# PCB_sterownika_pasek_LED.net
KiCad netlist of a schematic drawn in EAGLE
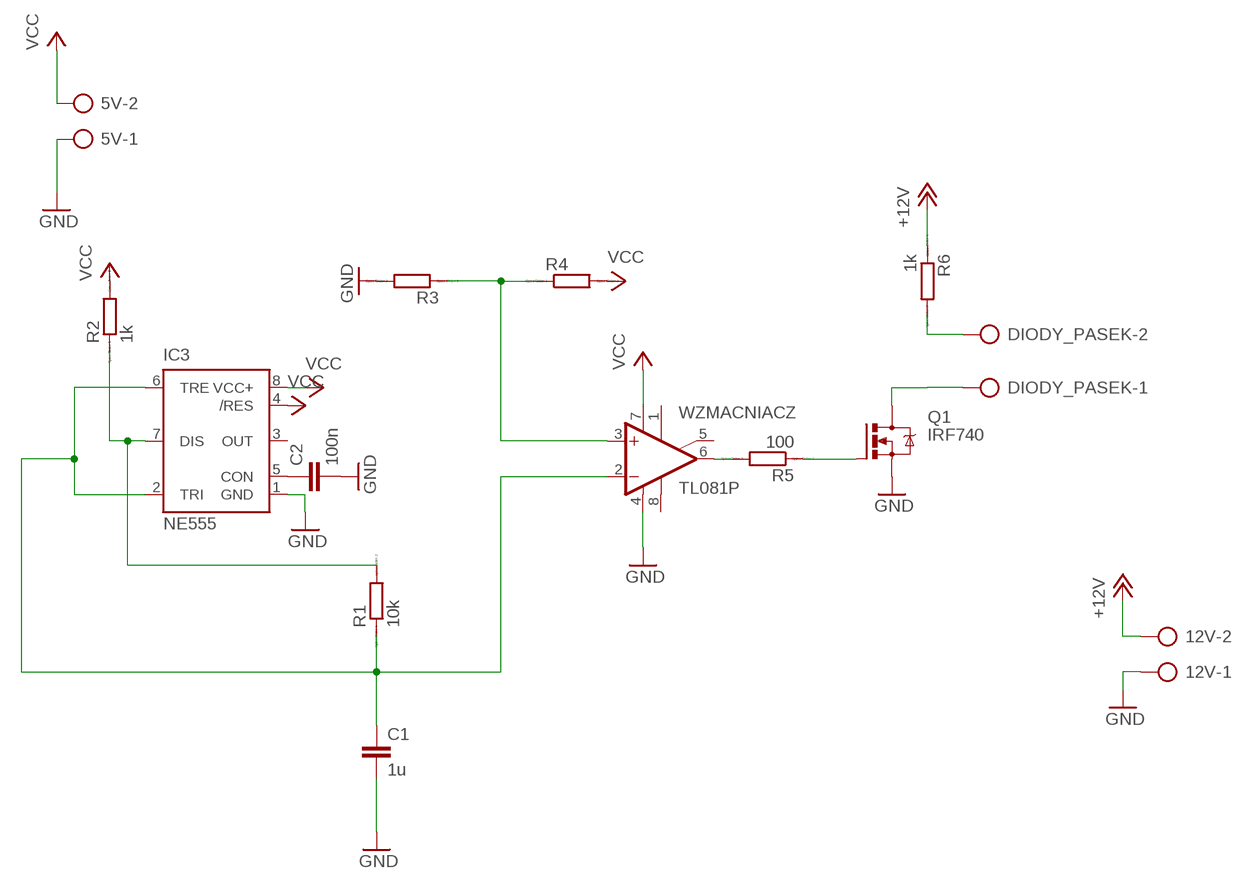
[diagram p0: schematic, sheet 1]

(export (version "E")
  (design (tool "Eeschema 10.0.6"))
  (components
    (comp (ref "5V")
      (value "AK500/2")
      (footprint "eagle-import:AK500_2")
      (libsource (lib "eagle-import") (part "AK500/2"))
    )
    (comp (ref "12V")
      (value "AK500/2")
      (footprint "eagle-import:AK500_2")
      (libsource (lib "eagle-import") (part "AK500/2"))
    )
    (comp (ref "C1")
      (value "1u")
      (footprint "eagle-import:C025-024X044")
      (libsource (lib "eagle-import") (part "C-EU025-024X044"))
    )
    (comp (ref "C2")
      (value "100n")
      (footprint "eagle-import:C025-024X044")
      (libsource (lib "eagle-import") (part "C-EU025-024X044"))
    )
    (comp (ref "DIODY_PASEK")
      (value "AK500/2")
      (footprint "eagle-import:AK500_2")
      (libsource (lib "eagle-import") (part "AK500/2"))
    )
    (comp (ref "IC3")
      (value "NE555")
      (footprint "eagle-import:DIL-08")
      (fields (field (name "MF") "Arrow Electronics") (field (name "MPN") "NE555N"))
      (libsource (lib "eagle-import") (part "NE555"))
    )
    (comp (ref "Q1")
      (value "IRF740")
      (footprint "eagle-import:TO220BV")
      (libsource (lib "eagle-import") (part "IRF740"))
    )
    (comp (ref "R1")
      (value "10k")
      (footprint "eagle-import:0204_7")
      (libsource (lib "eagle-import") (part "R0204/7"))
    )
    (comp (ref "R2")
      (value "1k")
      (footprint "eagle-import:0204_7")
      (libsource (lib "eagle-import") (part "R0204/7"))
    )
    (comp (ref "R3")
      (value "R0204/7")
      (footprint "eagle-import:0204_7")
      (libsource (lib "eagle-import") (part "R0204/7"))
    )
    (comp (ref "R4")
      (value "R0204/7")
      (footprint "eagle-import:0204_7")
      (libsource (lib "eagle-import") (part "R0204/7"))
    )
    (comp (ref "R5")
      (value "100")
      (footprint "eagle-import:0204_7")
      (libsource (lib "eagle-import") (part "R0204/7"))
    )
    (comp (ref "R6")
      (value "1k")
      (footprint "eagle-import:0204_7")
      (libsource (lib "eagle-import") (part "R0204/7"))
    )
    (comp (ref "WZMACNIACZ")
      (value "TL081P")
      (footprint "eagle-import:DIL08")
      (libsource (lib "eagle-import") (part "TL081P"))
    )
  )
  (nets
    (net (code "1") (name "+12V") (class "Default")
      (node (ref "12V") (pin "2") (pinfunction "KL_2") (pintype "passive"))
      (node (ref "R6") (pin "1") (pinfunction "1_1") (pintype "passive"))
    )
    (net (code "2") (name "GND") (class "Default")
      (node (ref "12V") (pin "1") (pinfunction "KL_1") (pintype "passive"))
      (node (ref "5V") (pin "1") (pinfunction "KL_1") (pintype "passive"))
      (node (ref "C1") (pin "2") (pinfunction "2_2") (pintype "passive"))
      (node (ref "C2") (pin "2") (pinfunction "2_2") (pintype "passive"))
      (node (ref "IC3") (pin "1") (pinfunction "GND_1") (pintype "power_in"))
      (node (ref "Q1") (pin "S") (pinfunction "S_S") (pintype "passive"))
      (node (ref "R3") (pin "2") (pinfunction "2_2") (pintype "passive"))
      (node (ref "WZMACNIACZ") (pin "4") (pinfunction "V-_4") (pintype "power_in"))
    )
    (net (code "3") (name "Net-(DIODY_PASEKA-KL)") (class "Default")
      (node (ref "DIODY_PASEK") (pin "1") (pinfunction "KL_1") (pintype "passive"))
      (node (ref "Q1") (pin "D") (pinfunction "D_D") (pintype "passive"))
    )
    (net (code "4") (name "Net-(DIODY_PASEKB-KL)") (class "Default")
      (node (ref "DIODY_PASEK") (pin "2") (pinfunction "KL_2") (pintype "passive"))
      (node (ref "R6") (pin "2") (pinfunction "2_2") (pintype "passive"))
    )
    (net (code "5") (name "Net-(IC3-CON)") (class "Default")
      (node (ref "C2") (pin "1") (pinfunction "1_1") (pintype "passive"))
      (node (ref "IC3") (pin "5") (pinfunction "CON_5") (pintype "input"))
    )
    (net (code "6") (name "Net-(IC3-DIS)") (class "Default")
      (node (ref "IC3") (pin "7") (pinfunction "DIS_7") (pintype "input"))
      (node (ref "R1") (pin "2") (pinfunction "2_2") (pintype "passive"))
      (node (ref "R2") (pin "1") (pinfunction "1_1") (pintype "passive"))
    )
    (net (code "7") (name "Net-(IC3-TRE)") (class "Default")
      (node (ref "C1") (pin "1") (pinfunction "1_1") (pintype "passive"))
      (node (ref "IC3") (pin "2") (pinfunction "TRI_2") (pintype "input"))
      (node (ref "IC3") (pin "6") (pinfunction "TRE_6") (pintype "input"))
      (node (ref "R1") (pin "1") (pinfunction "1_1") (pintype "passive"))
      (node (ref "WZMACNIACZ") (pin "2") (pinfunction "-IN_2") (pintype "input"))
    )
    (net (code "8") (name "Net-(Q1-PadG)") (class "Default")
      (node (ref "Q1") (pin "G") (pinfunction "G_G") (pintype "passive"))
      (node (ref "R5") (pin "1") (pinfunction "1_1") (pintype "passive"))
    )
    (net (code "9") (name "Net-(WZMACNIACZ-+IN)") (class "Default")
      (node (ref "R3") (pin "1") (pinfunction "1_1") (pintype "passive"))
      (node (ref "R4") (pin "1") (pinfunction "1_1") (pintype "passive"))
      (node (ref "WZMACNIACZ") (pin "3") (pinfunction "+IN_3") (pintype "input"))
    )
    (net (code "10") (name "Net-(WZMACNIACZ-OUT)") (class "Default")
      (node (ref "R5") (pin "2") (pinfunction "2_2") (pintype "passive"))
      (node (ref "WZMACNIACZ") (pin "6") (pinfunction "OUT_6") (pintype "output"))
    )
    (net (code "11") (name "VCC") (class "Default")
      (node (ref "5V") (pin "2") (pinfunction "KL_2") (pintype "passive"))
      (node (ref "IC3") (pin "4") (pinfunction "/RES_4") (pintype "input"))
      (node (ref "IC3") (pin "8") (pinfunction "VCC+_8") (pintype "power_in"))
      (node (ref "R2") (pin "2") (pinfunction "2_2") (pintype "passive"))
      (node (ref "R4") (pin "2") (pinfunction "2_2") (pintype "passive"))
      (node (ref "WZMACNIACZ") (pin "7") (pinfunction "V+_7") (pintype "power_in"))
    )
    (net (code "12") (name "unconnected-(IC3-OUT-Pad3)") (class "Default")
      (node (ref "IC3") (pin "3") (pinfunction "OUT_3") (pintype "output"))
    )
    (net (code "13") (name "unconnected-(WZMACNIACZ-ON1-Pad1)") (class "Default")
      (node (ref "WZMACNIACZ") (pin "1") (pinfunction "ON1_1") (pintype "passive"))
    )
    (net (code "14") (name "unconnected-(WZMACNIACZ-ON2-Pad5)") (class "Default")
      (node (ref "WZMACNIACZ") (pin "5") (pinfunction "ON2_5") (pintype "passive"))
    )
    (net (code "15") (name "unconnected-(WZMACNIACZ-OPT-Pad8)") (class "Default")
      (node (ref "WZMACNIACZ") (pin "8") (pinfunction "OPT_8") (pintype "passive"))
    )
  )
)
